# Sheet1.net
KiCad netlist of a schematic drawn in Altium Designer
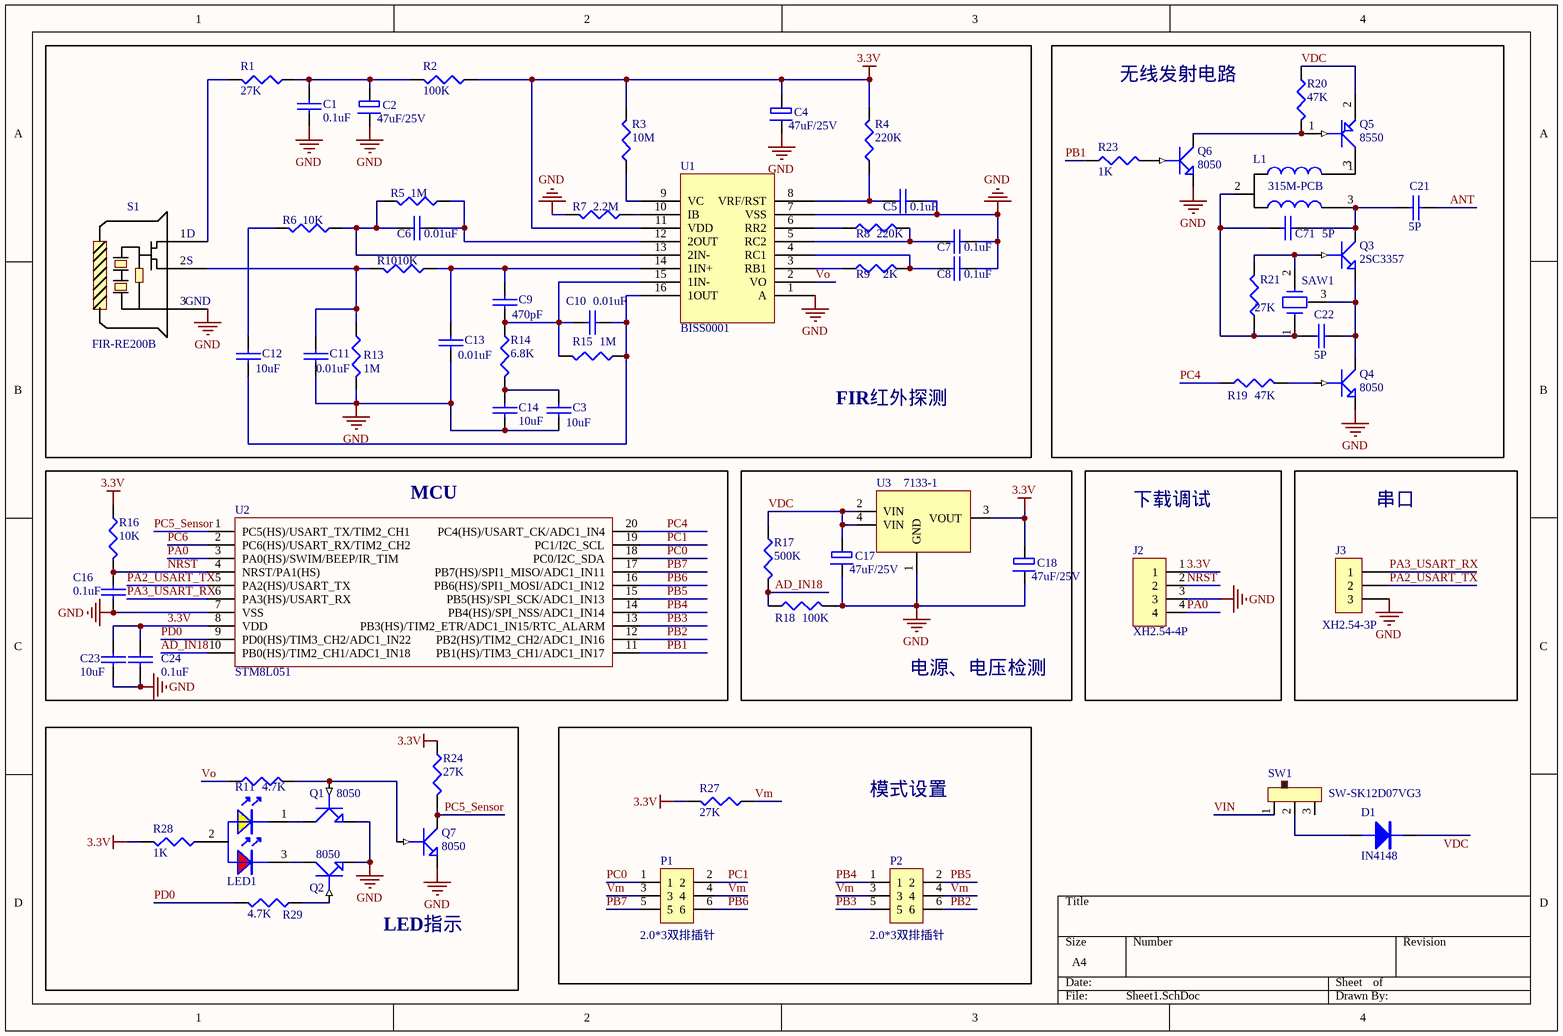
[diagram p0: Sheet1.SchDoc]

(export (version "E")
  (design (tool "Eeschema 10.0.6"))
  (components
    (comp (ref "C1")
      (value "0.1uF")
      (footprint "0603")
      (description "0603陶瓷贴片电容")
      (libsource (lib "INSPUR_PCB") (part "CAP-0603"))
    )
    (comp (ref "C2")
      (value "47uF/25V")
      (footprint "RB2.54 5*11")
      (description "铝电解电容")
      (libsource (lib "INSPUR_PCB") (part "47uF/25V"))
    )
    (comp (ref "C3")
      (value "10uF")
      (footprint "0805")
      (description "0805陶瓷贴片电容")
      (libsource (lib "INSPUR_PCB") (part "CAP-0805"))
    )
    (comp (ref "C4")
      (value "47uF/25V")
      (footprint "RB2.54 5*11")
      (description "铝电解电容")
      (libsource (lib "INSPUR_PCB") (part "47uF/25V"))
    )
    (comp (ref "C5")
      (value "0.1uF")
      (footprint "0603")
      (description "0603陶瓷贴片电容")
      (libsource (lib "INSPUR_PCB") (part "CAP-0603"))
    )
    (comp (ref "C6")
      (value "0.01uF")
      (footprint "0603")
      (description "0603陶瓷贴片电容")
      (libsource (lib "INSPUR_PCB") (part "CAP-0603"))
    )
    (comp (ref "C7")
      (value "0.1uF")
      (footprint "0603")
      (description "0603陶瓷贴片电容")
      (libsource (lib "INSPUR_PCB") (part "CAP-0603"))
    )
    (comp (ref "C8")
      (value "0.1uF")
      (footprint "0603")
      (description "0603陶瓷贴片电容")
      (libsource (lib "INSPUR_PCB") (part "CAP-0603"))
    )
    (comp (ref "C9")
      (value "470pF")
      (footprint "0603")
      (description "0603陶瓷贴片电容")
      (libsource (lib "INSPUR_PCB") (part "CAP-0603"))
    )
    (comp (ref "C10")
      (value "0.01uF")
      (footprint "0603")
      (description "0603陶瓷贴片电容")
      (libsource (lib "INSPUR_PCB") (part "CAP-0603"))
    )
    (comp (ref "C11")
      (value "0.01uF")
      (footprint "0603")
      (description "0603陶瓷贴片电容")
      (libsource (lib "INSPUR_PCB") (part "CAP-0603"))
    )
    (comp (ref "C12")
      (value "10uF")
      (footprint "0805")
      (description "0805陶瓷贴片电容")
      (libsource (lib "INSPUR_PCB") (part "CAP-0805"))
    )
    (comp (ref "C13")
      (value "0.01uF")
      (footprint "0603")
      (description "0603陶瓷贴片电容")
      (libsource (lib "INSPUR_PCB") (part "CAP-0603"))
    )
    (comp (ref "C14")
      (value "10uF")
      (footprint "0805")
      (description "0805陶瓷贴片电容")
      (libsource (lib "INSPUR_PCB") (part "CAP-0805"))
    )
    (comp (ref "C16")
      (value "0.1uF")
      (footprint "0603")
      (description "0603陶瓷贴片电容")
      (libsource (lib "INSPUR_PCB") (part "CAP-0603"))
    )
    (comp (ref "C17")
      (value "47uF/25V")
      (footprint "RB2.54 5*11")
      (description "铝电解电容")
      (libsource (lib "INSPUR_PCB") (part "47uF/25V"))
    )
    (comp (ref "C18")
      (value "47uF/25V")
      (footprint "RB2.54 5*11")
      (description "铝电解电容")
      (libsource (lib "INSPUR_PCB") (part "47uF/25V"))
    )
    (comp (ref "C21") (value "5P") (footprint "0603") (libsource (lib "INSPUR_SCH") (part "CAP")))
    (comp (ref "C22") (value "5P") (footprint "0603") (libsource (lib "INSPUR_SCH") (part "CAP")))
    (comp (ref "C23")
      (value "10uF")
      (footprint "0805")
      (description "0805陶瓷贴片电容")
      (libsource (lib "INSPUR_PCB") (part "CAP-0805"))
    )
    (comp (ref "C24")
      (value "0.1uF")
      (footprint "0603")
      (description "0603陶瓷贴片电容")
      (libsource (lib "INSPUR_PCB") (part "CAP-0603"))
    )
    (comp (ref "C71") (value "5P") (footprint "0603") (libsource (lib "INSPUR_SCH") (part "CAP")))
    (comp (ref "D1")
      (value "IN4148")
      (footprint "SOD-123")
      (description "IN4148开关二极管")
      (libsource (lib "INSPUR_PCB") (part "IN4148"))
    )
    (comp (ref "J2")
      (value "XH2.54-4P")
      (footprint "2.54-4")
      (description "XH2.54-4P 白色插座")
      (libsource (lib "INSPUR_PCB") (part "XH2.54-4P"))
    )
    (comp (ref "J3")
      (value "XH2.54-3P")
      (footprint "2.54-3")
      (description "XH2.54-3P 白色母座")
      (libsource (lib "INSPUR_PCB") (part "XH2.54-3P"))
    )
    (comp (ref "L1")
      (value "315M-PCB")
      (footprint "315M-PCB")
      (description "板载PCB天线")
      (libsource (lib "INSPUR_PCB") (part "315M-PCB"))
    )
    (comp (ref "LED1")
      (value "红黄LED")
      (footprint "LED-K")
      (description "3mm共阳极 双色红黄LED")
      (libsource (lib "INSPUR_PCB") (part "LED2"))
    )
    (comp (ref "P1")
      (value "2.0*3双排插针")
      (footprint "2.0*3*2")
      (description "2.0mm*3   双排插针")
      (libsource (lib "INSPUR_PCB") (part "2.0*3双排插针"))
    )
    (comp (ref "P2")
      (value "2.0*3双排插针")
      (footprint "2.0*3*2")
      (description "2.0mm*3   双排插针")
      (libsource (lib "INSPUR_PCB") (part "2.0*3双排插针"))
    )
    (comp (ref "Q1")
      (value "8050")
      (footprint "SOT-23")
      (description "8050 NPN型三极管")
      (libsource (lib "INSPUR_PCB") (part "8050"))
    )
    (comp (ref "Q2")
      (value "8050")
      (footprint "SOT-23")
      (description "8050 NPN型三极管")
      (libsource (lib "INSPUR_PCB") (part "8050"))
    )
    (comp (ref "Q3")
      (value "2SC3357")
      (footprint "SOT-23")
      (description "2SC3357 高频二极管")
      (libsource (lib "INSPUR_PCB") (part "2SC3357"))
    )
    (comp (ref "Q4")
      (value "8050")
      (footprint "SOT-23")
      (description "8050 NPN型三极管")
      (libsource (lib "INSPUR_PCB") (part "8050"))
    )
    (comp (ref "Q5")
      (value "8550")
      (footprint "SOT-23")
      (description "8550  PNP三极管")
      (libsource (lib "INSPUR_PCB") (part "8550"))
    )
    (comp (ref "Q6")
      (value "8050")
      (footprint "SOT-23")
      (description "8050 NPN型三极管")
      (libsource (lib "INSPUR_PCB") (part "8050"))
    )
    (comp (ref "Q7")
      (value "8050")
      (footprint "SOT-23")
      (description "8050 NPN型三极管")
      (libsource (lib "INSPUR_PCB") (part "8050"))
    )
    (comp (ref "R1")
      (value "27K")
      (footprint "0603")
      (description "陶瓷贴片电阻0603封装")
      (libsource (lib "INSPUR_PCB") (part "RES-0603"))
    )
    (comp (ref "R2")
      (value "100K")
      (footprint "0603")
      (description "陶瓷贴片电阻0603封装")
      (libsource (lib "INSPUR_PCB") (part "RES-0603"))
    )
    (comp (ref "R3")
      (value "10M")
      (footprint "0603")
      (description "陶瓷贴片电阻0603封装")
      (libsource (lib "INSPUR_PCB") (part "RES-0603"))
    )
    (comp (ref "R4")
      (value "220K")
      (footprint "0603")
      (description "陶瓷贴片电阻0603封装")
      (libsource (lib "INSPUR_PCB") (part "RES-0603"))
    )
    (comp (ref "R5")
      (value "1M")
      (footprint "0603")
      (description "陶瓷贴片电阻0603封装")
      (libsource (lib "INSPUR_PCB") (part "RES-0603"))
    )
    (comp (ref "R6")
      (value "10K")
      (footprint "0603")
      (description "陶瓷贴片电阻0603封装")
      (libsource (lib "INSPUR_PCB") (part "RES-0603"))
    )
    (comp (ref "R7")
      (value "2.2M")
      (footprint "0603")
      (description "陶瓷贴片电阻0603封装")
      (libsource (lib "INSPUR_PCB") (part "RES-0603"))
    )
    (comp (ref "R8")
      (value "220K")
      (footprint "0603")
      (description "陶瓷贴片电阻0603封装")
      (libsource (lib "INSPUR_PCB") (part "RES-0603"))
    )
    (comp (ref "R9")
      (value "2K")
      (footprint "0603")
      (description "陶瓷贴片电阻0603封装")
      (libsource (lib "INSPUR_PCB") (part "RES-0603"))
    )
    (comp (ref "R10")
      (value "10K")
      (footprint "0603")
      (description "陶瓷贴片电阻0603封装")
      (libsource (lib "INSPUR_PCB") (part "RES-0603"))
    )
    (comp (ref "R11")
      (value "4.7K")
      (footprint "0603")
      (description "陶瓷贴片电阻0603封装")
      (libsource (lib "INSPUR_PCB") (part "RES-0603"))
    )
    (comp (ref "R13")
      (value "1M")
      (footprint "0603")
      (description "陶瓷贴片电阻0603封装")
      (libsource (lib "INSPUR_PCB") (part "RES-0603"))
    )
    (comp (ref "R14")
      (value "6.8K")
      (footprint "0603")
      (description "陶瓷贴片电阻0603封装")
      (libsource (lib "INSPUR_PCB") (part "RES-0603"))
    )
    (comp (ref "R15")
      (value "1M")
      (footprint "0603")
      (description "陶瓷贴片电阻0603封装")
      (libsource (lib "INSPUR_PCB") (part "RES-0603"))
    )
    (comp (ref "R16")
      (value "10K")
      (footprint "0603")
      (description "陶瓷贴片电阻0603封装")
      (libsource (lib "INSPUR_PCB") (part "RES-0603"))
    )
    (comp (ref "R17")
      (value "500K")
      (footprint "0603")
      (description "陶瓷贴片电阻0603封装")
      (libsource (lib "INSPUR_PCB") (part "RES-0603"))
    )
    (comp (ref "R18")
      (value "100K")
      (footprint "0603")
      (description "陶瓷贴片电阻0603封装")
      (libsource (lib "INSPUR_PCB") (part "RES-0603"))
    )
    (comp (ref "R19")
      (value "47K")
      (footprint "0603")
      (description "陶瓷贴片电阻0603封装")
      (libsource (lib "INSPUR_PCB") (part "RES-0603"))
    )
    (comp (ref "R20")
      (value "47K")
      (footprint "0603")
      (description "陶瓷贴片电阻0603封装")
      (libsource (lib "INSPUR_PCB") (part "RES-0603"))
    )
    (comp (ref "R21") (value "27K") (footprint "0603") (libsource (lib "INSPUR_SCH") (part "RES1")))
    (comp (ref "R23")
      (value "1K")
      (footprint "0603")
      (description "陶瓷贴片电阻0603封装")
      (libsource (lib "INSPUR_PCB") (part "RES-0603"))
    )
    (comp (ref "R24")
      (value "27K")
      (footprint "0603")
      (description "陶瓷贴片电阻0603封装")
      (libsource (lib "INSPUR_PCB") (part "RES-0603"))
    )
    (comp (ref "R27")
      (value "27K")
      (footprint "0603")
      (description "陶瓷贴片电阻0603封装")
      (libsource (lib "INSPUR_PCB") (part "RES-0603"))
    )
    (comp (ref "R28")
      (value "1K")
      (footprint "0603")
      (description "陶瓷贴片电阻0603封装")
      (libsource (lib "INSPUR_PCB") (part "RES-0603"))
    )
    (comp (ref "R29")
      (value "4.7K")
      (footprint "0603")
      (description "陶瓷贴片电阻0603封装")
      (libsource (lib "INSPUR_PCB") (part "RES-0603"))
    )
    (comp (ref "S1")
      (value "FIR-RE200B")
      (footprint "TO-39")
      (libsource (lib "INSPUR_SCH") (part "FIR-RE200B"))
    )
    (comp (ref "SAW1")
      (value "CRYSTAL(表面接地)")
      (footprint "TO-39")
      (description "R315A  声表")
      (libsource (lib "INSPUR_PCB") (part "CRYSTAL(表面接地)"))
    )
    (comp (ref "SW1")
      (value "SW-SK12D07VG3")
      (footprint "SW-SK12D07VG3")
      (description "SK12D07VG3")
      (libsource (lib "INSPUR_PCB") (part "SW-SK12D07VG3"))
    )
    (comp (ref "U1") (value "BISS0001") (footprint "SO-16") (libsource (lib "INSPUR_SCH") (part "BISS0001")))
    (comp (ref "U2")
      (value "STM8L051")
      (footprint "TSSOP20")
      (description "单片机")
      (libsource (lib "mylib") (part "STM8L051"))
    )
    (comp (ref "U3")
      (value "7133-1")
      (footprint "SOT-89")
      (description "7133-1   3.3V  LDO电源芯片")
      (libsource (lib "INSPUR_PCB") (part "7133-1"))
    )
  )
  (nets
    (net (code "1") (name "/AD_IN18") (class "Default")
      (node (ref "R17") (pin "2") (pinfunction "2_2") (pintype "passive"))
      (node (ref "R18") (pin "1") (pinfunction "1_1") (pintype "passive"))
      (node (ref "U2") (pin "10") (pinfunction "PB0(HS)/TIM2_CH1/ADC1_IN18_10") (pintype "passive"))
    )
    (net (code "2") (name "/ANT") (class "Default")
      (node (ref "C21") (pin "2") (pinfunction "2_2") (pintype "passive"))
    )
    (net (code "3") (name "/NRST") (class "Default")
      (node (ref "C16") (pin "2") (pinfunction "2_2") (pintype "passive"))
      (node (ref "J2") (pin "2") (pinfunction "2_2") (pintype "passive"))
      (node (ref "R16") (pin "2") (pinfunction "2_2") (pintype "passive"))
      (node (ref "U2") (pin "4") (pinfunction "NRST/PA1(HS)_4") (pintype "passive"))
    )
    (net (code "4") (name "/PA0") (class "Default")
      (node (ref "J2") (pin "4") (pinfunction "4_4") (pintype "passive"))
      (node (ref "U2") (pin "3") (pinfunction "PA0(HS)/SWIM/BEEP/IR_TIM_3") (pintype "passive"))
    )
    (net (code "5") (name "/PA2_USART_TX") (class "Default")
      (node (ref "J3") (pin "2") (pinfunction "2_2") (pintype "passive"))
      (node (ref "U2") (pin "5") (pinfunction "PA2(HS)/USART_TX_5") (pintype "passive"))
    )
    (net (code "6") (name "/PA3_USART_RX") (class "Default")
      (node (ref "J3") (pin "1") (pinfunction "1_1") (pintype "passive"))
      (node (ref "U2") (pin "6") (pinfunction "PA3(HS)/USART_RX_6") (pintype "passive"))
    )
    (net (code "7") (name "/PB1") (class "Default")
      (node (ref "R23") (pin "1") (pinfunction "1_1") (pintype "passive"))
      (node (ref "U2") (pin "11") (pinfunction "PB1(HS)/TIM3_CH1/ADC1_IN17_11") (pintype "passive"))
    )
    (net (code "8") (name "/PB2") (class "Default")
      (node (ref "P2") (pin "6") (pinfunction "6_6") (pintype "passive"))
      (node (ref "U2") (pin "12") (pinfunction "PB2(HS)/TIM2_CH2/ADC1_IN16_12") (pintype "passive"))
    )
    (net (code "9") (name "/PB3") (class "Default")
      (node (ref "P2") (pin "5") (pinfunction "5_5") (pintype "passive"))
      (node (ref "U2") (pin "13") (pinfunction "PB3(HS)/TIM2_ETR/ADC1_IN15/RTC_ALARM_13") (pintype "passive"))
    )
    (net (code "10") (name "/PB4") (class "Default")
      (node (ref "P2") (pin "1") (pinfunction "1_1") (pintype "passive"))
      (node (ref "U2") (pin "14") (pinfunction "PB4(HS)/SPI_NSS/ADC1_IN14_14") (pintype "passive"))
    )
    (net (code "11") (name "/PB5") (class "Default")
      (node (ref "P2") (pin "2") (pinfunction "2_2") (pintype "passive"))
      (node (ref "U2") (pin "15") (pinfunction "PB5(HS)/SPI_SCK/ADC1_IN13_15") (pintype "passive"))
    )
    (net (code "12") (name "/PB6") (class "Default")
      (node (ref "P1") (pin "6") (pinfunction "6_6") (pintype "passive"))
      (node (ref "U2") (pin "16") (pinfunction "PB6(HS)/SPI1_MOSI/ADC1_IN12_16") (pintype "passive"))
    )
    (net (code "13") (name "/PB7") (class "Default")
      (node (ref "P1") (pin "5") (pinfunction "5_5") (pintype "passive"))
      (node (ref "U2") (pin "17") (pinfunction "PB7(HS)/SPI1_MISO/ADC1_IN11_17") (pintype "passive"))
    )
    (net (code "14") (name "/PC0") (class "Default")
      (node (ref "P1") (pin "1") (pinfunction "1_1") (pintype "passive"))
      (node (ref "U2") (pin "18") (pinfunction "PC0/I2C_SDA_18") (pintype "passive"))
    )
    (net (code "15") (name "/PC1") (class "Default")
      (node (ref "P1") (pin "2") (pinfunction "2_2") (pintype "passive"))
      (node (ref "U2") (pin "19") (pinfunction "PC1/I2C_SCL_19") (pintype "passive"))
    )
    (net (code "16") (name "/PC4") (class "Default")
      (node (ref "R19") (pin "1") (pinfunction "1_1") (pintype "passive"))
      (node (ref "U2") (pin "20") (pinfunction "PC4(HS)/USART_CK/ADC1_IN4_20") (pintype "passive"))
    )
    (net (code "17") (name "/PC5_Sensor") (class "Default")
      (node (ref "Q7") (pin "3") (pinfunction "C_3") (pintype "passive"))
      (node (ref "R24") (pin "2") (pinfunction "2_2") (pintype "passive"))
      (node (ref "U2") (pin "1") (pinfunction "PC5(HS)/USART_TX/TIM2_CH1_1") (pintype "passive"))
    )
    (net (code "18") (name "/PC6") (class "Default")
      (node (ref "U2") (pin "2") (pinfunction "PC6(HS)/USART_RX/TIM2_CH2_2") (pintype "passive"))
    )
    (net (code "19") (name "/PD0") (class "Default")
      (node (ref "R29") (pin "2") (pinfunction "2_2") (pintype "passive"))
      (node (ref "U2") (pin "9") (pinfunction "PD0(HS)/TIM3_CH2/ADC1_IN22_9") (pintype "passive"))
    )
    (net (code "20") (name "/VDC") (class "Default")
      (node (ref "C17") (pin "1") (pintype "passive"))
      (node (ref "D1") (pin "2") (pinfunction "K_2") (pintype "passive"))
      (node (ref "Q5") (pin "2") (pinfunction "E_2") (pintype "passive"))
      (node (ref "R17") (pin "1") (pinfunction "1_1") (pintype "passive"))
      (node (ref "R20") (pin "1") (pinfunction "1_1") (pintype "passive"))
      (node (ref "U3") (pin "2") (pinfunction "VIN_2") (pintype "passive"))
      (node (ref "U3") (pin "4") (pinfunction "VIN_4") (pintype "passive"))
    )
    (net (code "21") (name "/VIN") (class "Default")
      (node (ref "SW1") (pin "1") (pinfunction "5_1") (pintype "passive"))
    )
    (net (code "22") (name "/Vm") (class "Default")
      (node (ref "P1") (pin "3") (pinfunction "3_3") (pintype "passive"))
      (node (ref "P1") (pin "4") (pinfunction "4_4") (pintype "passive"))
      (node (ref "P2") (pin "3") (pinfunction "3_3") (pintype "passive"))
      (node (ref "P2") (pin "4") (pinfunction "4_4") (pintype "passive"))
      (node (ref "R27") (pin "1") (pinfunction "1_1") (pintype "passive"))
    )
    (net (code "23") (name "/Vo") (class "Default")
      (node (ref "R11") (pin "1") (pinfunction "1_1") (pintype "passive"))
      (node (ref "U1") (pin "2") (pinfunction "VO_2") (pintype "passive"))
    )
    (net (code "24") (name "3.3V") (class "Default")
      (node (ref "C18") (pin "1") (pintype "passive"))
      (node (ref "C23") (pin "2") (pinfunction "2_2") (pintype "passive"))
      (node (ref "C24") (pin "2") (pinfunction "2_2") (pintype "passive"))
      (node (ref "C4") (pin "1") (pintype "passive"))
      (node (ref "J2") (pin "1") (pinfunction "1_1") (pintype "passive"))
      (node (ref "R16") (pin "1") (pinfunction "1_1") (pintype "passive"))
      (node (ref "R2") (pin "1") (pinfunction "1_1") (pintype "passive"))
      (node (ref "R24") (pin "1") (pinfunction "1_1") (pintype "passive"))
      (node (ref "R27") (pin "2") (pinfunction "2_2") (pintype "passive"))
      (node (ref "R28") (pin "2") (pinfunction "2_2") (pintype "passive"))
      (node (ref "R3") (pin "2") (pinfunction "2_2") (pintype "passive"))
      (node (ref "R4") (pin "2") (pinfunction "2_2") (pintype "passive"))
      (node (ref "U1") (pin "11") (pinfunction "VDD_11") (pintype "passive"))
      (node (ref "U2") (pin "8") (pinfunction "VDD_8") (pintype "passive"))
      (node (ref "U3") (pin "3") (pinfunction "VOUT_3") (pintype "passive"))
    )
    (net (code "25") (name "GND") (class "Default")
      (node (ref "C1") (pin "1") (pinfunction "1_1") (pintype "passive"))
      (node (ref "C11") (pin "2") (pinfunction "2_2") (pintype "passive"))
      (node (ref "C13") (pin "2") (pinfunction "2_2") (pintype "passive"))
      (node (ref "C14") (pin "1") (pinfunction "1_1") (pintype "passive"))
      (node (ref "C16") (pin "1") (pinfunction "1_1") (pintype "passive"))
      (node (ref "C17") (pin "2") (pintype "passive"))
      (node (ref "C18") (pin "2") (pintype "passive"))
      (node (ref "C2") (pin "2") (pintype "passive"))
      (node (ref "C23") (pin "1") (pinfunction "1_1") (pintype "passive"))
      (node (ref "C24") (pin "1") (pinfunction "1_1") (pintype "passive"))
      (node (ref "C3") (pin "1") (pinfunction "1_1") (pintype "passive"))
      (node (ref "C4") (pin "2") (pintype "passive"))
      (node (ref "C5") (pin "2") (pinfunction "2_2") (pintype "passive"))
      (node (ref "C7") (pin "2") (pinfunction "2_2") (pintype "passive"))
      (node (ref "C8") (pin "2") (pinfunction "2_2") (pintype "passive"))
      (node (ref "J2") (pin "3") (pinfunction "3_3") (pintype "passive"))
      (node (ref "J3") (pin "3") (pinfunction "3_3") (pintype "passive"))
      (node (ref "Q1") (pin "2") (pinfunction "E_2") (pintype "passive"))
      (node (ref "Q2") (pin "2") (pinfunction "E_2") (pintype "passive"))
      (node (ref "Q4") (pin "2") (pinfunction "E_2") (pintype "passive"))
      (node (ref "Q6") (pin "2") (pinfunction "E_2") (pintype "passive"))
      (node (ref "Q7") (pin "2") (pinfunction "E_2") (pintype "passive"))
      (node (ref "R13") (pin "2") (pinfunction "2_2") (pintype "passive"))
      (node (ref "R18") (pin "2") (pinfunction "2_2") (pintype "passive"))
      (node (ref "R7") (pin "2") (pinfunction "2_2") (pintype "passive"))
      (node (ref "S1") (pin "3") (pintype "passive"))
      (node (ref "U1") (pin "1") (pinfunction "A_1") (pintype "passive"))
      (node (ref "U1") (pin "7") (pinfunction "VSS_7") (pintype "passive"))
      (node (ref "U2") (pin "7") (pinfunction "VSS_7") (pintype "passive"))
      (node (ref "U3") (pin "1") (pinfunction "GND_1") (pintype "passive"))
    )
    (net (code "26") (name "Net-(C1-Pad2)") (class "Default")
      (node (ref "C1") (pin "2") (pinfunction "2_2") (pintype "passive"))
      (node (ref "C2") (pin "1") (pintype "passive"))
      (node (ref "R1") (pin "1") (pinfunction "1_1") (pintype "passive"))
      (node (ref "R2") (pin "2") (pinfunction "2_2") (pintype "passive"))
    )
    (net (code "27") (name "Net-(C11-Pad1)") (class "Default")
      (node (ref "C11") (pin "1") (pinfunction "1_1") (pintype "passive"))
      (node (ref "R10") (pin "2") (pinfunction "2_2") (pintype "passive"))
      (node (ref "R13") (pin "1") (pinfunction "1_1") (pintype "passive"))
      (node (ref "S1") (pin "2") (pintype "passive"))
    )
    (net (code "28") (name "Net-(C12-Pad1)") (class "Default")
      (node (ref "C12") (pin "1") (pinfunction "1_1") (pintype "passive"))
      (node (ref "R6") (pin "2") (pinfunction "2_2") (pintype "passive"))
    )
    (net (code "29") (name "Net-(C14-Pad2)") (class "Default")
      (node (ref "C14") (pin "2") (pinfunction "2_2") (pintype "passive"))
      (node (ref "C3") (pin "2") (pinfunction "2_2") (pintype "passive"))
      (node (ref "R14") (pin "2") (pinfunction "2_2") (pintype "passive"))
    )
    (net (code "30") (name "Net-(D1-A)") (class "Default")
      (node (ref "D1") (pin "1") (pinfunction "A_1") (pintype "passive"))
      (node (ref "SW1") (pin "2") (pinfunction "6_2") (pintype "passive"))
    )
    (net (code "31") (name "Net-(L1-L1)") (class "Default")
      (node (ref "L1") (pin "1") (pinfunction "L1_1") (pintype "passive"))
      (node (ref "Q5") (pin "3") (pinfunction "C_3") (pintype "passive"))
    )
    (net (code "32") (name "Net-(L1-L2)") (class "Default")
      (node (ref "C22") (pin "2") (pinfunction "2_2") (pintype "passive"))
      (node (ref "C71") (pin "1") (pinfunction "1_1") (pintype "passive"))
      (node (ref "L1") (pin "2") (pinfunction "L2_2") (pintype "passive"))
      (node (ref "R21") (pin "1") (pinfunction "1_1") (pintype "passive"))
      (node (ref "SAW1") (pin "1") (pinfunction "1_1") (pintype "passive"))
    )
    (net (code "33") (name "Net-(L1-L3)") (class "Default")
      (node (ref "C21") (pin "1") (pinfunction "1_1") (pintype "passive"))
      (node (ref "C71") (pin "2") (pinfunction "2_2") (pintype "passive"))
      (node (ref "L1") (pin "3") (pinfunction "L3_3") (pintype "passive"))
      (node (ref "Q3") (pin "3") (pinfunction "C_3") (pintype "passive"))
    )
    (net (code "34") (name "Net-(LED1-A)") (class "Default")
      (node (ref "LED1") (pin "2") (pinfunction "A_2") (pintype "passive"))
      (node (ref "R28") (pin "1") (pinfunction "1_1") (pintype "passive"))
    )
    (net (code "35") (name "Net-(LED1-R)") (class "Default")
      (node (ref "LED1") (pin "3") (pinfunction "R_3") (pintype "passive"))
      (node (ref "Q2") (pin "3") (pinfunction "C_3") (pintype "passive"))
    )
    (net (code "36") (name "Net-(LED1-Y)") (class "Default")
      (node (ref "LED1") (pin "1") (pinfunction "Y_1") (pintype "passive"))
      (node (ref "Q1") (pin "3") (pinfunction "C_3") (pintype "passive"))
    )
    (net (code "37") (name "Net-(Q1-B)") (class "Default")
      (node (ref "Q1") (pin "1") (pinfunction "B_1") (pintype "input"))
      (node (ref "Q7") (pin "1") (pinfunction "B_1") (pintype "input"))
      (node (ref "R11") (pin "2") (pinfunction "2_2") (pintype "passive"))
    )
    (net (code "38") (name "Net-(Q2-B)") (class "Default")
      (node (ref "Q2") (pin "1") (pinfunction "B_1") (pintype "input"))
      (node (ref "R29") (pin "1") (pinfunction "1_1") (pintype "passive"))
    )
    (net (code "39") (name "Net-(Q3-B)") (class "Default")
      (node (ref "Q3") (pin "1") (pinfunction "B_1") (pintype "input"))
      (node (ref "R21") (pin "2") (pinfunction "2_2") (pintype "passive"))
      (node (ref "SAW1") (pin "2") (pinfunction "2_2") (pintype "passive"))
    )
    (net (code "40") (name "Net-(Q3-E)") (class "Default")
      (node (ref "C22") (pin "1") (pinfunction "1_1") (pintype "passive"))
      (node (ref "Q3") (pin "2") (pinfunction "E_2") (pintype "passive"))
      (node (ref "Q4") (pin "3") (pinfunction "C_3") (pintype "passive"))
      (node (ref "SAW1") (pin "3") (pinfunction "GND_3") (pintype "passive"))
    )
    (net (code "41") (name "Net-(Q4-B)") (class "Default")
      (node (ref "Q4") (pin "1") (pinfunction "B_1") (pintype "input"))
      (node (ref "R19") (pin "2") (pinfunction "2_2") (pintype "passive"))
    )
    (net (code "42") (name "Net-(Q5-B)") (class "Default")
      (node (ref "Q5") (pin "1") (pinfunction "B_1") (pintype "input"))
      (node (ref "Q6") (pin "3") (pinfunction "C_3") (pintype "passive"))
      (node (ref "R20") (pin "2") (pinfunction "2_2") (pintype "passive"))
    )
    (net (code "43") (name "Net-(Q6-B)") (class "Default")
      (node (ref "Q6") (pin "1") (pinfunction "B_1") (pintype "input"))
      (node (ref "R23") (pin "2") (pinfunction "2_2") (pintype "passive"))
    )
    (net (code "44") (name "Net-(R1-Pad2)") (class "Default")
      (node (ref "R1") (pin "2") (pinfunction "2_2") (pintype "passive"))
      (node (ref "S1") (pin "1") (pintype "passive"))
    )
    (net (code "45") (name "Net-(U1-1IN+)") (class "Default")
      (node (ref "C13") (pin "1") (pinfunction "1_1") (pintype "passive"))
      (node (ref "C9") (pin "1") (pinfunction "1_1") (pintype "passive"))
      (node (ref "R10") (pin "1") (pinfunction "1_1") (pintype "passive"))
      (node (ref "U1") (pin "14") (pinfunction "1IN+_14") (pintype "passive"))
    )
    (net (code "46") (name "Net-(U1-1IN-)") (class "Default")
      (node (ref "C10") (pin "2") (pinfunction "2_2") (pintype "passive"))
      (node (ref "C9") (pin "2") (pinfunction "2_2") (pintype "passive"))
      (node (ref "R14") (pin "1") (pinfunction "1_1") (pintype "passive"))
      (node (ref "R15") (pin "2") (pinfunction "2_2") (pintype "passive"))
      (node (ref "U1") (pin "15") (pinfunction "1IN-_15") (pintype "passive"))
    )
    (net (code "47") (name "Net-(U1-1OUT)") (class "Default")
      (node (ref "C10") (pin "1") (pinfunction "1_1") (pintype "passive"))
      (node (ref "C12") (pin "2") (pinfunction "2_2") (pintype "passive"))
      (node (ref "R15") (pin "1") (pinfunction "1_1") (pintype "passive"))
      (node (ref "U1") (pin "16") (pinfunction "1OUT_16") (pintype "passive"))
    )
    (net (code "48") (name "Net-(U1-2IN-)") (class "Default")
      (node (ref "C6") (pin "2") (pinfunction "2_2") (pintype "passive"))
      (node (ref "R5") (pin "2") (pinfunction "2_2") (pintype "passive"))
      (node (ref "R6") (pin "1") (pinfunction "1_1") (pintype "passive"))
      (node (ref "U1") (pin "13") (pinfunction "2IN-_13") (pintype "passive"))
    )
    (net (code "49") (name "Net-(U1-2OUT)") (class "Default")
      (node (ref "C6") (pin "1") (pinfunction "1_1") (pintype "passive"))
      (node (ref "R5") (pin "1") (pinfunction "1_1") (pintype "passive"))
      (node (ref "U1") (pin "12") (pinfunction "2OUT_12") (pintype "passive"))
    )
    (net (code "50") (name "Net-(U1-IB)") (class "Default")
      (node (ref "R7") (pin "1") (pinfunction "1_1") (pintype "passive"))
      (node (ref "U1") (pin "10") (pinfunction "IB_10") (pintype "passive"))
    )
    (net (code "51") (name "Net-(U1-RB1)") (class "Default")
      (node (ref "R9") (pin "1") (pinfunction "1_1") (pintype "passive"))
      (node (ref "U1") (pin "3") (pinfunction "RB1_3") (pintype "passive"))
    )
    (net (code "52") (name "Net-(U1-RC1)") (class "Default")
      (node (ref "C8") (pin "1") (pinfunction "1_1") (pintype "passive"))
      (node (ref "R9") (pin "2") (pinfunction "2_2") (pintype "passive"))
      (node (ref "U1") (pin "4") (pinfunction "RC1_4") (pintype "passive"))
    )
    (net (code "53") (name "Net-(U1-RC2)") (class "Default")
      (node (ref "C7") (pin "1") (pinfunction "1_1") (pintype "passive"))
      (node (ref "R8") (pin "2") (pinfunction "2_2") (pintype "passive"))
      (node (ref "U1") (pin "5") (pinfunction "RC2_5") (pintype "passive"))
    )
    (net (code "54") (name "Net-(U1-RR2)") (class "Default")
      (node (ref "R8") (pin "1") (pinfunction "1_1") (pintype "passive"))
      (node (ref "U1") (pin "6") (pinfunction "RR2_6") (pintype "passive"))
    )
    (net (code "55") (name "Net-(U1-VC)") (class "Default")
      (node (ref "R3") (pin "1") (pinfunction "1_1") (pintype "passive"))
      (node (ref "U1") (pin "9") (pinfunction "VC_9") (pintype "passive"))
    )
    (net (code "56") (name "Net-(U1-VRF{slash}RST)") (class "Default")
      (node (ref "C5") (pin "1") (pinfunction "1_1") (pintype "passive"))
      (node (ref "R4") (pin "1") (pinfunction "1_1") (pintype "passive"))
      (node (ref "U1") (pin "8") (pinfunction "VRF/RST_8") (pintype "passive"))
    )
    (net (code "57") (name "unconnected-(SW1-7-Pad3)") (class "Default")
      (node (ref "SW1") (pin "3") (pinfunction "7_3") (pintype "passive"))
    )
  )
)
